# Sheet5.net
KiCad netlist of a schematic drawn in Altium Designer
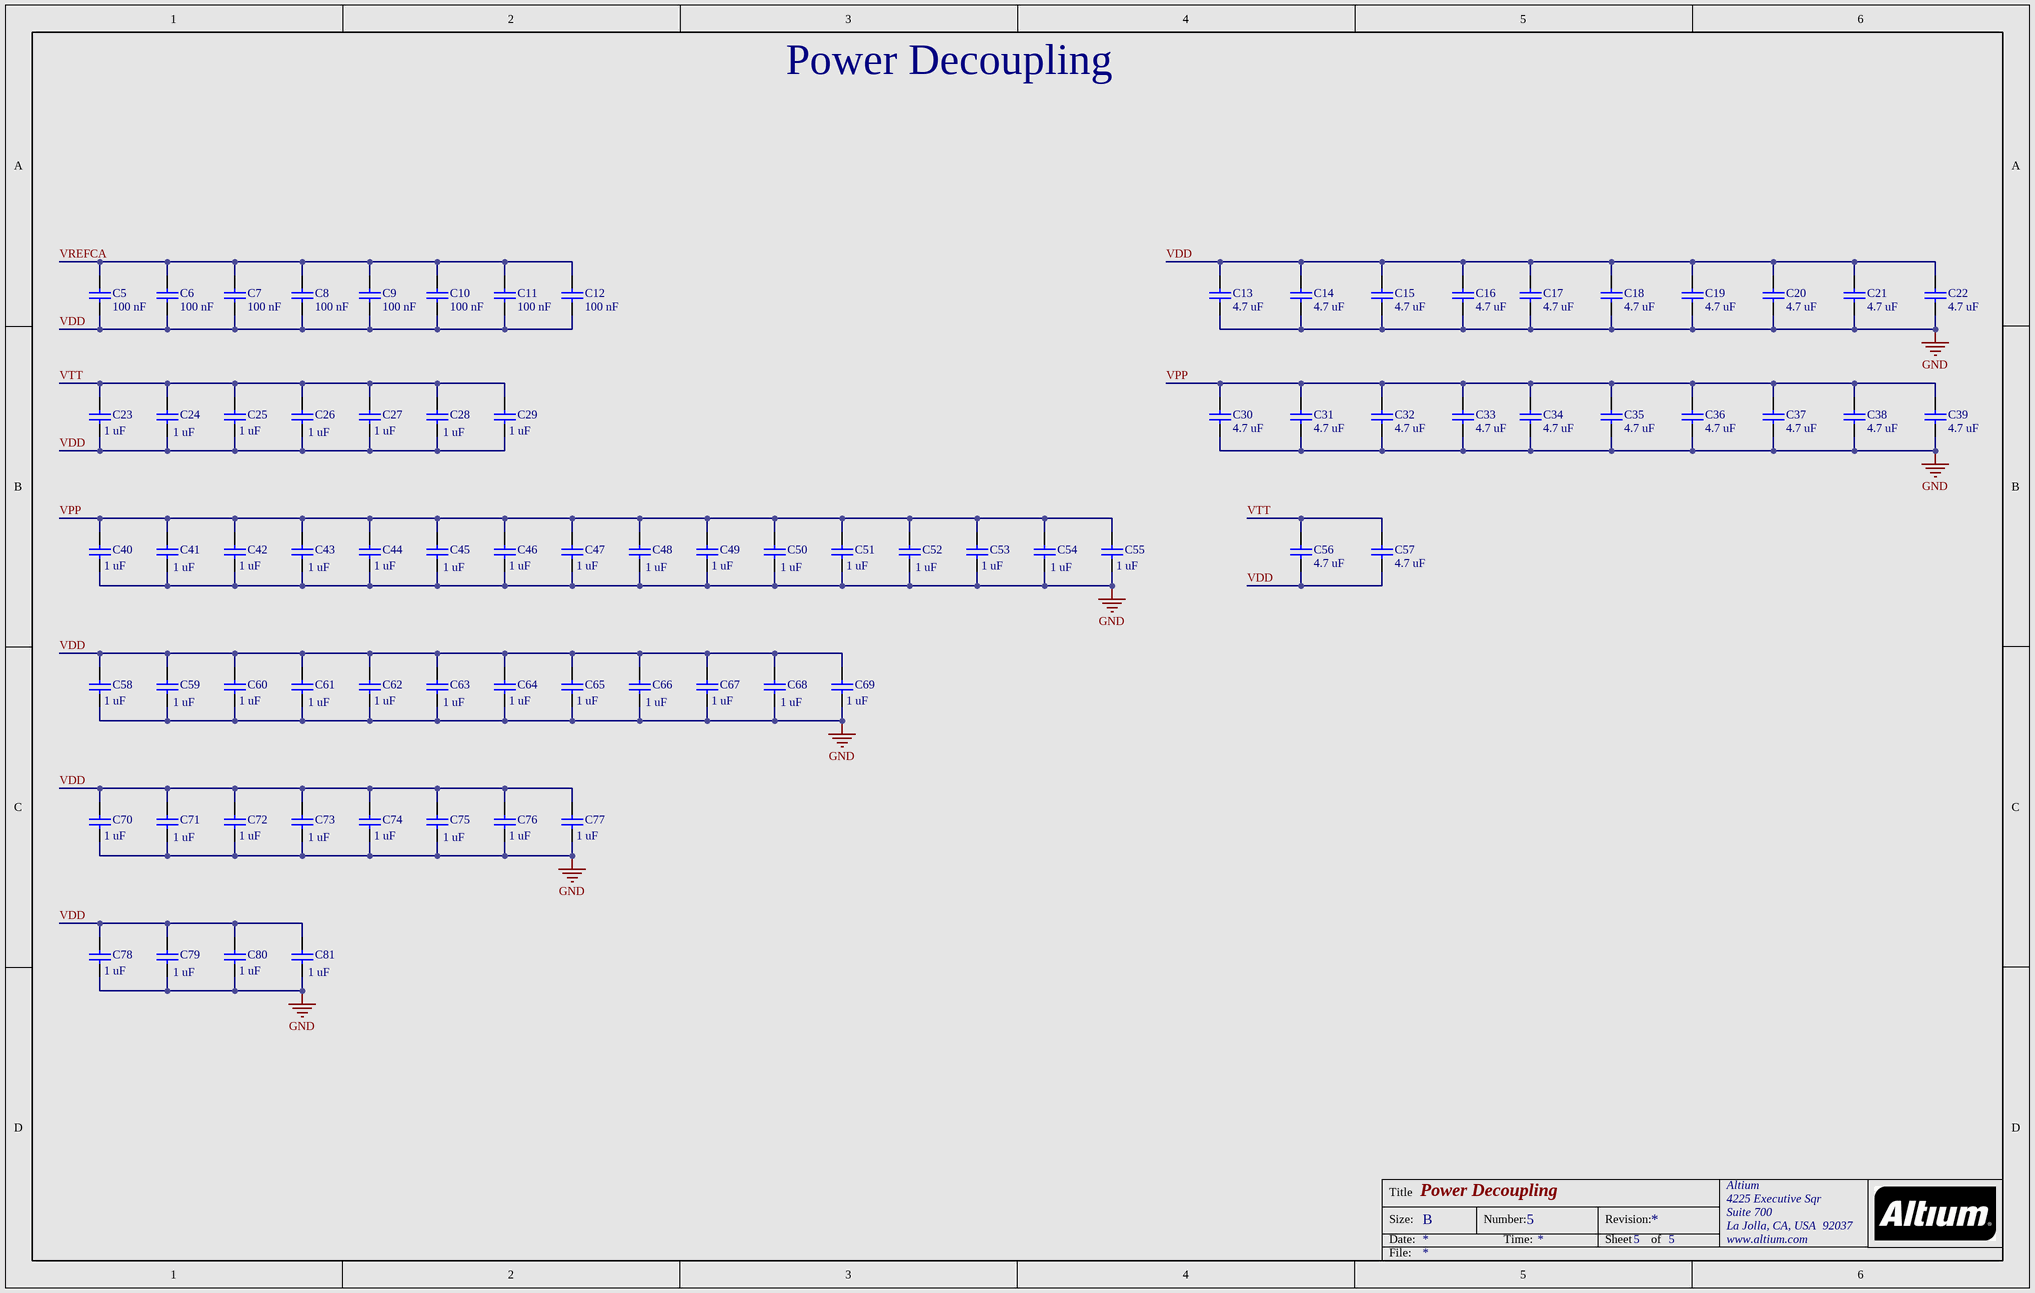
[diagram p0: Sheet5.SchDoc]

(export (version "E")
  (design (tool "Eeschema 10.0.6"))
  (components
    (comp (ref "C5")
      (value "C1005X7R1E104M")
      (footprint "CAPC1005X55X10LL05")
      (description "Chip Capacitor, 0.1 uF, +/- 20%, 25 V, -55 to 125 degC, 0402 (1005 Metric), RoHS, Tape and Reel")
      (fields (field (name "TOLERANCE") "20%") (field (name "CAPACITANCE") "100 nF"))
      (libsource (lib "Altium Content Vault") (part "CMP-1663-00009-2"))
    )
    (comp (ref "C6")
      (value "C1005X7R1E104M")
      (footprint "CAPC1005X55X10LL05")
      (description "Chip Capacitor, 0.1 uF, +/- 20%, 25 V, -55 to 125 degC, 0402 (1005 Metric), RoHS, Tape and Reel")
      (fields (field (name "TOLERANCE") "20%") (field (name "CAPACITANCE") "100 nF"))
      (libsource (lib "Altium Content Vault") (part "CMP-1663-00009-2"))
    )
    (comp (ref "C7")
      (value "C1005X7R1E104M")
      (footprint "CAPC1005X55X10LL05")
      (description "Chip Capacitor, 0.1 uF, +/- 20%, 25 V, -55 to 125 degC, 0402 (1005 Metric), RoHS, Tape and Reel")
      (fields (field (name "TOLERANCE") "20%") (field (name "CAPACITANCE") "100 nF"))
      (libsource (lib "Altium Content Vault") (part "CMP-1663-00009-2"))
    )
    (comp (ref "C8")
      (value "C1005X7R1E104M")
      (footprint "CAPC1005X55X10LL05")
      (description "Chip Capacitor, 0.1 uF, +/- 20%, 25 V, -55 to 125 degC, 0402 (1005 Metric), RoHS, Tape and Reel")
      (fields (field (name "TOLERANCE") "20%") (field (name "CAPACITANCE") "100 nF"))
      (libsource (lib "Altium Content Vault") (part "CMP-1663-00009-2"))
    )
    (comp (ref "C9")
      (value "C1005X7R1E104M")
      (footprint "CAPC1005X55X10LL05")
      (description "Chip Capacitor, 0.1 uF, +/- 20%, 25 V, -55 to 125 degC, 0402 (1005 Metric), RoHS, Tape and Reel")
      (fields (field (name "TOLERANCE") "20%") (field (name "CAPACITANCE") "100 nF"))
      (libsource (lib "Altium Content Vault") (part "CMP-1663-00009-2"))
    )
    (comp (ref "C10")
      (value "C1005X7R1E104M")
      (footprint "CAPC1005X55X10LL05")
      (description "Chip Capacitor, 0.1 uF, +/- 20%, 25 V, -55 to 125 degC, 0402 (1005 Metric), RoHS, Tape and Reel")
      (fields (field (name "TOLERANCE") "20%") (field (name "CAPACITANCE") "100 nF"))
      (libsource (lib "Altium Content Vault") (part "CMP-1663-00009-2"))
    )
    (comp (ref "C11")
      (value "C1005X7R1E104M")
      (footprint "CAPC1005X55X10LL05")
      (description "Chip Capacitor, 0.1 uF, +/- 20%, 25 V, -55 to 125 degC, 0402 (1005 Metric), RoHS, Tape and Reel")
      (fields (field (name "TOLERANCE") "20%") (field (name "CAPACITANCE") "100 nF"))
      (libsource (lib "Altium Content Vault") (part "CMP-1663-00009-2"))
    )
    (comp (ref "C12")
      (value "C1005X7R1E104M")
      (footprint "CAPC1005X55X10LL05")
      (description "Chip Capacitor, 0.1 uF, +/- 20%, 25 V, -55 to 125 degC, 0402 (1005 Metric), RoHS, Tape and Reel")
      (fields (field (name "TOLERANCE") "20%") (field (name "CAPACITANCE") "100 nF"))
      (libsource (lib "Altium Content Vault") (part "CMP-1663-00009-2"))
    )
    (comp (ref "C13")
      (value "GRM188R60J475KE19D")
      (footprint "CAPC1608X90X35ML10T15")
      (description "Chip Capacitor, 4.7 uF, +/- 10%, 6.3 V, -55 to 85 degC, 0603 (1608 Metric), RoHS, Tape and Reel")
      (fields (field (name "TOLERANCE") "10%") (field (name "CAPACITANCE") "4.7 uF"))
      (libsource (lib "Altium Content Vault") (part "CMP-2006-02799-2"))
    )
    (comp (ref "C14")
      (value "GRM188R60J475KE19D")
      (footprint "CAPC1608X90X35ML10T15")
      (description "Chip Capacitor, 4.7 uF, +/- 10%, 6.3 V, -55 to 85 degC, 0603 (1608 Metric), RoHS, Tape and Reel")
      (fields (field (name "TOLERANCE") "10%") (field (name "CAPACITANCE") "4.7 uF"))
      (libsource (lib "Altium Content Vault") (part "CMP-2006-02799-2"))
    )
    (comp (ref "C15")
      (value "GRM188R60J475KE19D")
      (footprint "CAPC1608X90X35ML10T15")
      (description "Chip Capacitor, 4.7 uF, +/- 10%, 6.3 V, -55 to 85 degC, 0603 (1608 Metric), RoHS, Tape and Reel")
      (fields (field (name "TOLERANCE") "10%") (field (name "CAPACITANCE") "4.7 uF"))
      (libsource (lib "Altium Content Vault") (part "CMP-2006-02799-2"))
    )
    (comp (ref "C16")
      (value "GRM188R60J475KE19D")
      (footprint "CAPC1608X90X35ML10T15")
      (description "Chip Capacitor, 4.7 uF, +/- 10%, 6.3 V, -55 to 85 degC, 0603 (1608 Metric), RoHS, Tape and Reel")
      (fields (field (name "TOLERANCE") "10%") (field (name "CAPACITANCE") "4.7 uF"))
      (libsource (lib "Altium Content Vault") (part "CMP-2006-02799-2"))
    )
    (comp (ref "C17")
      (value "GRM188R60J475KE19D")
      (footprint "CAPC1608X90X35ML10T15")
      (description "Chip Capacitor, 4.7 uF, +/- 10%, 6.3 V, -55 to 85 degC, 0603 (1608 Metric), RoHS, Tape and Reel")
      (fields (field (name "TOLERANCE") "10%") (field (name "CAPACITANCE") "4.7 uF"))
      (libsource (lib "Altium Content Vault") (part "CMP-2006-02799-2"))
    )
    (comp (ref "C18")
      (value "GRM188R60J475KE19D")
      (footprint "CAPC1608X90X35ML10T15")
      (description "Chip Capacitor, 4.7 uF, +/- 10%, 6.3 V, -55 to 85 degC, 0603 (1608 Metric), RoHS, Tape and Reel")
      (fields (field (name "TOLERANCE") "10%") (field (name "CAPACITANCE") "4.7 uF"))
      (libsource (lib "Altium Content Vault") (part "CMP-2006-02799-2"))
    )
    (comp (ref "C19")
      (value "GRM188R60J475KE19D")
      (footprint "CAPC1608X90X35ML10T15")
      (description "Chip Capacitor, 4.7 uF, +/- 10%, 6.3 V, -55 to 85 degC, 0603 (1608 Metric), RoHS, Tape and Reel")
      (fields (field (name "TOLERANCE") "10%") (field (name "CAPACITANCE") "4.7 uF"))
      (libsource (lib "Altium Content Vault") (part "CMP-2006-02799-2"))
    )
    (comp (ref "C20")
      (value "GRM188R60J475KE19D")
      (footprint "CAPC1608X90X35ML10T15")
      (description "Chip Capacitor, 4.7 uF, +/- 10%, 6.3 V, -55 to 85 degC, 0603 (1608 Metric), RoHS, Tape and Reel")
      (fields (field (name "TOLERANCE") "10%") (field (name "CAPACITANCE") "4.7 uF"))
      (libsource (lib "Altium Content Vault") (part "CMP-2006-02799-2"))
    )
    (comp (ref "C21")
      (value "GRM188R60J475KE19D")
      (footprint "CAPC1608X90X35ML10T15")
      (description "Chip Capacitor, 4.7 uF, +/- 10%, 6.3 V, -55 to 85 degC, 0603 (1608 Metric), RoHS, Tape and Reel")
      (fields (field (name "TOLERANCE") "10%") (field (name "CAPACITANCE") "4.7 uF"))
      (libsource (lib "Altium Content Vault") (part "CMP-2006-02799-2"))
    )
    (comp (ref "C22")
      (value "GRM188R60J475KE19D")
      (footprint "CAPC1608X90X35ML10T15")
      (description "Chip Capacitor, 4.7 uF, +/- 10%, 6.3 V, -55 to 85 degC, 0603 (1608 Metric), RoHS, Tape and Reel")
      (fields (field (name "TOLERANCE") "10%") (field (name "CAPACITANCE") "4.7 uF"))
      (libsource (lib "Altium Content Vault") (part "CMP-2006-02799-2"))
    )
    (comp (ref "C23")
      (value "CGB2A1X5R1E105K033BC")
      (footprint "CAPC1005X33X10LL5")
      (description "Chip Capacitor, 1 uF, +/- 10%, 25 V, -55 to 85 degC, 0402 (1005 Metric), RoHS, Tape and Reel")
      (fields (field (name "CAPACITANCE") "1 uF") (field (name "TOLERANCE") "10%"))
      (libsource (lib "Altium Content Vault") (part "CMP-1663-00006-2"))
    )
    (comp (ref "C24")
      (value "CGB2A1X5R1E105K033BC")
      (footprint "CAPC1005X33X10LL5")
      (description "Chip Capacitor, 1 uF, +/- 10%, 25 V, -55 to 85 degC, 0402 (1005 Metric), RoHS, Tape and Reel")
      (fields (field (name "CAPACITANCE") "1 uF") (field (name "TOLERANCE") "10%"))
      (libsource (lib "Altium Content Vault") (part "CMP-1663-00006-2"))
    )
    (comp (ref "C25")
      (value "CGB2A1X5R1E105K033BC")
      (footprint "CAPC1005X33X10LL5")
      (description "Chip Capacitor, 1 uF, +/- 10%, 25 V, -55 to 85 degC, 0402 (1005 Metric), RoHS, Tape and Reel")
      (fields (field (name "CAPACITANCE") "1 uF") (field (name "TOLERANCE") "10%"))
      (libsource (lib "Altium Content Vault") (part "CMP-1663-00006-2"))
    )
    (comp (ref "C26")
      (value "CGB2A1X5R1E105K033BC")
      (footprint "CAPC1005X33X10LL5")
      (description "Chip Capacitor, 1 uF, +/- 10%, 25 V, -55 to 85 degC, 0402 (1005 Metric), RoHS, Tape and Reel")
      (fields (field (name "CAPACITANCE") "1 uF") (field (name "TOLERANCE") "10%"))
      (libsource (lib "Altium Content Vault") (part "CMP-1663-00006-2"))
    )
    (comp (ref "C27")
      (value "CGB2A1X5R1E105K033BC")
      (footprint "CAPC1005X33X10LL5")
      (description "Chip Capacitor, 1 uF, +/- 10%, 25 V, -55 to 85 degC, 0402 (1005 Metric), RoHS, Tape and Reel")
      (fields (field (name "CAPACITANCE") "1 uF") (field (name "TOLERANCE") "10%"))
      (libsource (lib "Altium Content Vault") (part "CMP-1663-00006-2"))
    )
    (comp (ref "C28")
      (value "CGB2A1X5R1E105K033BC")
      (footprint "CAPC1005X33X10LL5")
      (description "Chip Capacitor, 1 uF, +/- 10%, 25 V, -55 to 85 degC, 0402 (1005 Metric), RoHS, Tape and Reel")
      (fields (field (name "CAPACITANCE") "1 uF") (field (name "TOLERANCE") "10%"))
      (libsource (lib "Altium Content Vault") (part "CMP-1663-00006-2"))
    )
    (comp (ref "C29")
      (value "CGB2A1X5R1E105K033BC")
      (footprint "CAPC1005X33X10LL5")
      (description "Chip Capacitor, 1 uF, +/- 10%, 25 V, -55 to 85 degC, 0402 (1005 Metric), RoHS, Tape and Reel")
      (fields (field (name "CAPACITANCE") "1 uF") (field (name "TOLERANCE") "10%"))
      (libsource (lib "Altium Content Vault") (part "CMP-1663-00006-2"))
    )
    (comp (ref "C30")
      (value "GRM188R60J475KE19D")
      (footprint "CAPC1608X90X35ML10T15")
      (description "Chip Capacitor, 4.7 uF, +/- 10%, 6.3 V, -55 to 85 degC, 0603 (1608 Metric), RoHS, Tape and Reel")
      (fields (field (name "TOLERANCE") "10%") (field (name "CAPACITANCE") "4.7 uF"))
      (libsource (lib "Altium Content Vault") (part "CMP-2006-02799-2"))
    )
    (comp (ref "C31")
      (value "GRM188R60J475KE19D")
      (footprint "CAPC1608X90X35ML10T15")
      (description "Chip Capacitor, 4.7 uF, +/- 10%, 6.3 V, -55 to 85 degC, 0603 (1608 Metric), RoHS, Tape and Reel")
      (fields (field (name "TOLERANCE") "10%") (field (name "CAPACITANCE") "4.7 uF"))
      (libsource (lib "Altium Content Vault") (part "CMP-2006-02799-2"))
    )
    (comp (ref "C32")
      (value "GRM188R60J475KE19D")
      (footprint "CAPC1608X90X35ML10T15")
      (description "Chip Capacitor, 4.7 uF, +/- 10%, 6.3 V, -55 to 85 degC, 0603 (1608 Metric), RoHS, Tape and Reel")
      (fields (field (name "TOLERANCE") "10%") (field (name "CAPACITANCE") "4.7 uF"))
      (libsource (lib "Altium Content Vault") (part "CMP-2006-02799-2"))
    )
    (comp (ref "C33")
      (value "GRM188R60J475KE19D")
      (footprint "CAPC1608X90X35ML10T15")
      (description "Chip Capacitor, 4.7 uF, +/- 10%, 6.3 V, -55 to 85 degC, 0603 (1608 Metric), RoHS, Tape and Reel")
      (fields (field (name "TOLERANCE") "10%") (field (name "CAPACITANCE") "4.7 uF"))
      (libsource (lib "Altium Content Vault") (part "CMP-2006-02799-2"))
    )
    (comp (ref "C34")
      (value "GRM188R60J475KE19D")
      (footprint "CAPC1608X90X35ML10T15")
      (description "Chip Capacitor, 4.7 uF, +/- 10%, 6.3 V, -55 to 85 degC, 0603 (1608 Metric), RoHS, Tape and Reel")
      (fields (field (name "TOLERANCE") "10%") (field (name "CAPACITANCE") "4.7 uF"))
      (libsource (lib "Altium Content Vault") (part "CMP-2006-02799-2"))
    )
    (comp (ref "C35")
      (value "GRM188R60J475KE19D")
      (footprint "CAPC1608X90X35ML10T15")
      (description "Chip Capacitor, 4.7 uF, +/- 10%, 6.3 V, -55 to 85 degC, 0603 (1608 Metric), RoHS, Tape and Reel")
      (fields (field (name "TOLERANCE") "10%") (field (name "CAPACITANCE") "4.7 uF"))
      (libsource (lib "Altium Content Vault") (part "CMP-2006-02799-2"))
    )
    (comp (ref "C36")
      (value "GRM188R60J475KE19D")
      (footprint "CAPC1608X90X35ML10T15")
      (description "Chip Capacitor, 4.7 uF, +/- 10%, 6.3 V, -55 to 85 degC, 0603 (1608 Metric), RoHS, Tape and Reel")
      (fields (field (name "TOLERANCE") "10%") (field (name "CAPACITANCE") "4.7 uF"))
      (libsource (lib "Altium Content Vault") (part "CMP-2006-02799-2"))
    )
    (comp (ref "C37")
      (value "GRM188R60J475KE19D")
      (footprint "CAPC1608X90X35ML10T15")
      (description "Chip Capacitor, 4.7 uF, +/- 10%, 6.3 V, -55 to 85 degC, 0603 (1608 Metric), RoHS, Tape and Reel")
      (fields (field (name "TOLERANCE") "10%") (field (name "CAPACITANCE") "4.7 uF"))
      (libsource (lib "Altium Content Vault") (part "CMP-2006-02799-2"))
    )
    (comp (ref "C38")
      (value "GRM188R60J475KE19D")
      (footprint "CAPC1608X90X35ML10T15")
      (description "Chip Capacitor, 4.7 uF, +/- 10%, 6.3 V, -55 to 85 degC, 0603 (1608 Metric), RoHS, Tape and Reel")
      (fields (field (name "TOLERANCE") "10%") (field (name "CAPACITANCE") "4.7 uF"))
      (libsource (lib "Altium Content Vault") (part "CMP-2006-02799-2"))
    )
    (comp (ref "C39")
      (value "GRM188R60J475KE19D")
      (footprint "CAPC1608X90X35ML10T15")
      (description "Chip Capacitor, 4.7 uF, +/- 10%, 6.3 V, -55 to 85 degC, 0603 (1608 Metric), RoHS, Tape and Reel")
      (fields (field (name "TOLERANCE") "10%") (field (name "CAPACITANCE") "4.7 uF"))
      (libsource (lib "Altium Content Vault") (part "CMP-2006-02799-2"))
    )
    (comp (ref "C40")
      (value "CGB2A1X5R1E105K033BC")
      (footprint "CAPC1005X33X10LL5")
      (description "Chip Capacitor, 1 uF, +/- 10%, 25 V, -55 to 85 degC, 0402 (1005 Metric), RoHS, Tape and Reel")
      (fields (field (name "CAPACITANCE") "1 uF") (field (name "TOLERANCE") "10%"))
      (libsource (lib "Altium Content Vault") (part "CMP-1663-00006-2"))
    )
    (comp (ref "C41")
      (value "CGB2A1X5R1E105K033BC")
      (footprint "CAPC1005X33X10LL5")
      (description "Chip Capacitor, 1 uF, +/- 10%, 25 V, -55 to 85 degC, 0402 (1005 Metric), RoHS, Tape and Reel")
      (fields (field (name "CAPACITANCE") "1 uF") (field (name "TOLERANCE") "10%"))
      (libsource (lib "Altium Content Vault") (part "CMP-1663-00006-2"))
    )
    (comp (ref "C42")
      (value "CGB2A1X5R1E105K033BC")
      (footprint "CAPC1005X33X10LL5")
      (description "Chip Capacitor, 1 uF, +/- 10%, 25 V, -55 to 85 degC, 0402 (1005 Metric), RoHS, Tape and Reel")
      (fields (field (name "CAPACITANCE") "1 uF") (field (name "TOLERANCE") "10%"))
      (libsource (lib "Altium Content Vault") (part "CMP-1663-00006-2"))
    )
    (comp (ref "C43")
      (value "CGB2A1X5R1E105K033BC")
      (footprint "CAPC1005X33X10LL5")
      (description "Chip Capacitor, 1 uF, +/- 10%, 25 V, -55 to 85 degC, 0402 (1005 Metric), RoHS, Tape and Reel")
      (fields (field (name "CAPACITANCE") "1 uF") (field (name "TOLERANCE") "10%"))
      (libsource (lib "Altium Content Vault") (part "CMP-1663-00006-2"))
    )
    (comp (ref "C44")
      (value "CGB2A1X5R1E105K033BC")
      (footprint "CAPC1005X33X10LL5")
      (description "Chip Capacitor, 1 uF, +/- 10%, 25 V, -55 to 85 degC, 0402 (1005 Metric), RoHS, Tape and Reel")
      (fields (field (name "CAPACITANCE") "1 uF") (field (name "TOLERANCE") "10%"))
      (libsource (lib "Altium Content Vault") (part "CMP-1663-00006-2"))
    )
    (comp (ref "C45")
      (value "CGB2A1X5R1E105K033BC")
      (footprint "CAPC1005X33X10LL5")
      (description "Chip Capacitor, 1 uF, +/- 10%, 25 V, -55 to 85 degC, 0402 (1005 Metric), RoHS, Tape and Reel")
      (fields (field (name "CAPACITANCE") "1 uF") (field (name "TOLERANCE") "10%"))
      (libsource (lib "Altium Content Vault") (part "CMP-1663-00006-2"))
    )
    (comp (ref "C46")
      (value "CGB2A1X5R1E105K033BC")
      (footprint "CAPC1005X33X10LL5")
      (description "Chip Capacitor, 1 uF, +/- 10%, 25 V, -55 to 85 degC, 0402 (1005 Metric), RoHS, Tape and Reel")
      (fields (field (name "CAPACITANCE") "1 uF") (field (name "TOLERANCE") "10%"))
      (libsource (lib "Altium Content Vault") (part "CMP-1663-00006-2"))
    )
    (comp (ref "C47")
      (value "CGB2A1X5R1E105K033BC")
      (footprint "CAPC1005X33X10LL5")
      (description "Chip Capacitor, 1 uF, +/- 10%, 25 V, -55 to 85 degC, 0402 (1005 Metric), RoHS, Tape and Reel")
      (fields (field (name "CAPACITANCE") "1 uF") (field (name "TOLERANCE") "10%"))
      (libsource (lib "Altium Content Vault") (part "CMP-1663-00006-2"))
    )
    (comp (ref "C48")
      (value "CGB2A1X5R1E105K033BC")
      (footprint "CAPC1005X33X10LL5")
      (description "Chip Capacitor, 1 uF, +/- 10%, 25 V, -55 to 85 degC, 0402 (1005 Metric), RoHS, Tape and Reel")
      (fields (field (name "CAPACITANCE") "1 uF") (field (name "TOLERANCE") "10%"))
      (libsource (lib "Altium Content Vault") (part "CMP-1663-00006-2"))
    )
    (comp (ref "C49")
      (value "CGB2A1X5R1E105K033BC")
      (footprint "CAPC1005X33X10LL5")
      (description "Chip Capacitor, 1 uF, +/- 10%, 25 V, -55 to 85 degC, 0402 (1005 Metric), RoHS, Tape and Reel")
      (fields (field (name "CAPACITANCE") "1 uF") (field (name "TOLERANCE") "10%"))
      (libsource (lib "Altium Content Vault") (part "CMP-1663-00006-2"))
    )
    (comp (ref "C50")
      (value "CGB2A1X5R1E105K033BC")
      (footprint "CAPC1005X33X10LL5")
      (description "Chip Capacitor, 1 uF, +/- 10%, 25 V, -55 to 85 degC, 0402 (1005 Metric), RoHS, Tape and Reel")
      (fields (field (name "CAPACITANCE") "1 uF") (field (name "TOLERANCE") "10%"))
      (libsource (lib "Altium Content Vault") (part "CMP-1663-00006-2"))
    )
    (comp (ref "C51")
      (value "CGB2A1X5R1E105K033BC")
      (footprint "CAPC1005X33X10LL5")
      (description "Chip Capacitor, 1 uF, +/- 10%, 25 V, -55 to 85 degC, 0402 (1005 Metric), RoHS, Tape and Reel")
      (fields (field (name "CAPACITANCE") "1 uF") (field (name "TOLERANCE") "10%"))
      (libsource (lib "Altium Content Vault") (part "CMP-1663-00006-2"))
    )
    (comp (ref "C52")
      (value "CGB2A1X5R1E105K033BC")
      (footprint "CAPC1005X33X10LL5")
      (description "Chip Capacitor, 1 uF, +/- 10%, 25 V, -55 to 85 degC, 0402 (1005 Metric), RoHS, Tape and Reel")
      (fields (field (name "CAPACITANCE") "1 uF") (field (name "TOLERANCE") "10%"))
      (libsource (lib "Altium Content Vault") (part "CMP-1663-00006-2"))
    )
    (comp (ref "C53")
      (value "CGB2A1X5R1E105K033BC")
      (footprint "CAPC1005X33X10LL5")
      (description "Chip Capacitor, 1 uF, +/- 10%, 25 V, -55 to 85 degC, 0402 (1005 Metric), RoHS, Tape and Reel")
      (fields (field (name "CAPACITANCE") "1 uF") (field (name "TOLERANCE") "10%"))
      (libsource (lib "Altium Content Vault") (part "CMP-1663-00006-2"))
    )
    (comp (ref "C54")
      (value "CGB2A1X5R1E105K033BC")
      (footprint "CAPC1005X33X10LL5")
      (description "Chip Capacitor, 1 uF, +/- 10%, 25 V, -55 to 85 degC, 0402 (1005 Metric), RoHS, Tape and Reel")
      (fields (field (name "CAPACITANCE") "1 uF") (field (name "TOLERANCE") "10%"))
      (libsource (lib "Altium Content Vault") (part "CMP-1663-00006-2"))
    )
    (comp (ref "C55")
      (value "CGB2A1X5R1E105K033BC")
      (footprint "CAPC1005X33X10LL5")
      (description "Chip Capacitor, 1 uF, +/- 10%, 25 V, -55 to 85 degC, 0402 (1005 Metric), RoHS, Tape and Reel")
      (fields (field (name "CAPACITANCE") "1 uF") (field (name "TOLERANCE") "10%"))
      (libsource (lib "Altium Content Vault") (part "CMP-1663-00006-2"))
    )
    (comp (ref "C56")
      (value "GRM188R60J475KE19D")
      (footprint "CAPC1608X90X35ML10T15")
      (description "Chip Capacitor, 4.7 uF, +/- 10%, 6.3 V, -55 to 85 degC, 0603 (1608 Metric), RoHS, Tape and Reel")
      (fields (field (name "TOLERANCE") "10%") (field (name "CAPACITANCE") "4.7 uF"))
      (libsource (lib "Altium Content Vault") (part "CMP-2006-02799-2"))
    )
    (comp (ref "C57")
      (value "GRM188R60J475KE19D")
      (footprint "CAPC1608X90X35ML10T15")
      (description "Chip Capacitor, 4.7 uF, +/- 10%, 6.3 V, -55 to 85 degC, 0603 (1608 Metric), RoHS, Tape and Reel")
      (fields (field (name "TOLERANCE") "10%") (field (name "CAPACITANCE") "4.7 uF"))
      (libsource (lib "Altium Content Vault") (part "CMP-2006-02799-2"))
    )
    (comp (ref "C58")
      (value "CGB2A1X5R1E105K033BC")
      (footprint "CAPC1005X33X10LL5")
      (description "Chip Capacitor, 1 uF, +/- 10%, 25 V, -55 to 85 degC, 0402 (1005 Metric), RoHS, Tape and Reel")
      (fields (field (name "CAPACITANCE") "1 uF") (field (name "TOLERANCE") "10%"))
      (libsource (lib "Altium Content Vault") (part "CMP-1663-00006-2"))
    )
    (comp (ref "C59")
      (value "CGB2A1X5R1E105K033BC")
      (footprint "CAPC1005X33X10LL5")
      (description "Chip Capacitor, 1 uF, +/- 10%, 25 V, -55 to 85 degC, 0402 (1005 Metric), RoHS, Tape and Reel")
      (fields (field (name "CAPACITANCE") "1 uF") (field (name "TOLERANCE") "10%"))
      (libsource (lib "Altium Content Vault") (part "CMP-1663-00006-2"))
    )
    (comp (ref "C60")
      (value "CGB2A1X5R1E105K033BC")
      (footprint "CAPC1005X33X10LL5")
      (description "Chip Capacitor, 1 uF, +/- 10%, 25 V, -55 to 85 degC, 0402 (1005 Metric), RoHS, Tape and Reel")
      (fields (field (name "CAPACITANCE") "1 uF") (field (name "TOLERANCE") "10%"))
      (libsource (lib "Altium Content Vault") (part "CMP-1663-00006-2"))
    )
    (comp (ref "C61")
      (value "CGB2A1X5R1E105K033BC")
      (footprint "CAPC1005X33X10LL5")
      (description "Chip Capacitor, 1 uF, +/- 10%, 25 V, -55 to 85 degC, 0402 (1005 Metric), RoHS, Tape and Reel")
      (fields (field (name "CAPACITANCE") "1 uF") (field (name "TOLERANCE") "10%"))
      (libsource (lib "Altium Content Vault") (part "CMP-1663-00006-2"))
    )
    (comp (ref "C62")
      (value "CGB2A1X5R1E105K033BC")
      (footprint "CAPC1005X33X10LL5")
      (description "Chip Capacitor, 1 uF, +/- 10%, 25 V, -55 to 85 degC, 0402 (1005 Metric), RoHS, Tape and Reel")
      (fields (field (name "CAPACITANCE") "1 uF") (field (name "TOLERANCE") "10%"))
      (libsource (lib "Altium Content Vault") (part "CMP-1663-00006-2"))
    )
    (comp (ref "C63")
      (value "CGB2A1X5R1E105K033BC")
      (footprint "CAPC1005X33X10LL5")
      (description "Chip Capacitor, 1 uF, +/- 10%, 25 V, -55 to 85 degC, 0402 (1005 Metric), RoHS, Tape and Reel")
      (fields (field (name "CAPACITANCE") "1 uF") (field (name "TOLERANCE") "10%"))
      (libsource (lib "Altium Content Vault") (part "CMP-1663-00006-2"))
    )
    (comp (ref "C64")
      (value "CGB2A1X5R1E105K033BC")
      (footprint "CAPC1005X33X10LL5")
      (description "Chip Capacitor, 1 uF, +/- 10%, 25 V, -55 to 85 degC, 0402 (1005 Metric), RoHS, Tape and Reel")
      (fields (field (name "CAPACITANCE") "1 uF") (field (name "TOLERANCE") "10%"))
      (libsource (lib "Altium Content Vault") (part "CMP-1663-00006-2"))
    )
    (comp (ref "C65")
      (value "CGB2A1X5R1E105K033BC")
      (footprint "CAPC1005X33X10LL5")
      (description "Chip Capacitor, 1 uF, +/- 10%, 25 V, -55 to 85 degC, 0402 (1005 Metric), RoHS, Tape and Reel")
      (fields (field (name "CAPACITANCE") "1 uF") (field (name "TOLERANCE") "10%"))
      (libsource (lib "Altium Content Vault") (part "CMP-1663-00006-2"))
    )
    (comp (ref "C66")
      (value "CGB2A1X5R1E105K033BC")
      (footprint "CAPC1005X33X10LL5")
      (description "Chip Capacitor, 1 uF, +/- 10%, 25 V, -55 to 85 degC, 0402 (1005 Metric), RoHS, Tape and Reel")
      (fields (field (name "CAPACITANCE") "1 uF") (field (name "TOLERANCE") "10%"))
      (libsource (lib "Altium Content Vault") (part "CMP-1663-00006-2"))
    )
    (comp (ref "C67")
      (value "CGB2A1X5R1E105K033BC")
      (footprint "CAPC1005X33X10LL5")
      (description "Chip Capacitor, 1 uF, +/- 10%, 25 V, -55 to 85 degC, 0402 (1005 Metric), RoHS, Tape and Reel")
      (fields (field (name "CAPACITANCE") "1 uF") (field (name "TOLERANCE") "10%"))
      (libsource (lib "Altium Content Vault") (part "CMP-1663-00006-2"))
    )
    (comp (ref "C68")
      (value "CGB2A1X5R1E105K033BC")
      (footprint "CAPC1005X33X10LL5")
      (description "Chip Capacitor, 1 uF, +/- 10%, 25 V, -55 to 85 degC, 0402 (1005 Metric), RoHS, Tape and Reel")
      (fields (field (name "CAPACITANCE") "1 uF") (field (name "TOLERANCE") "10%"))
      (libsource (lib "Altium Content Vault") (part "CMP-1663-00006-2"))
    )
    (comp (ref "C69")
      (value "CGB2A1X5R1E105K033BC")
      (footprint "CAPC1005X33X10LL5")
      (description "Chip Capacitor, 1 uF, +/- 10%, 25 V, -55 to 85 degC, 0402 (1005 Metric), RoHS, Tape and Reel")
      (fields (field (name "CAPACITANCE") "1 uF") (field (name "TOLERANCE") "10%"))
      (libsource (lib "Altium Content Vault") (part "CMP-1663-00006-2"))
    )
    (comp (ref "C70")
      (value "CGB2A1X5R1E105K033BC")
      (footprint "CAPC1005X33X10LL5")
      (description "Chip Capacitor, 1 uF, +/- 10%, 25 V, -55 to 85 degC, 0402 (1005 Metric), RoHS, Tape and Reel")
      (fields (field (name "CAPACITANCE") "1 uF") (field (name "TOLERANCE") "10%"))
      (libsource (lib "Altium Content Vault") (part "CMP-1663-00006-2"))
    )
    (comp (ref "C71")
      (value "CGB2A1X5R1E105K033BC")
      (footprint "CAPC1005X33X10LL5")
      (description "Chip Capacitor, 1 uF, +/- 10%, 25 V, -55 to 85 degC, 0402 (1005 Metric), RoHS, Tape and Reel")
      (fields (field (name "CAPACITANCE") "1 uF") (field (name "TOLERANCE") "10%"))
      (libsource (lib "Altium Content Vault") (part "CMP-1663-00006-2"))
    )
    (comp (ref "C72")
      (value "CGB2A1X5R1E105K033BC")
      (footprint "CAPC1005X33X10LL5")
      (description "Chip Capacitor, 1 uF, +/- 10%, 25 V, -55 to 85 degC, 0402 (1005 Metric), RoHS, Tape and Reel")
      (fields (field (name "CAPACITANCE") "1 uF") (field (name "TOLERANCE") "10%"))
      (libsource (lib "Altium Content Vault") (part "CMP-1663-00006-2"))
    )
    (comp (ref "C73")
      (value "CGB2A1X5R1E105K033BC")
      (footprint "CAPC1005X33X10LL5")
      (description "Chip Capacitor, 1 uF, +/- 10%, 25 V, -55 to 85 degC, 0402 (1005 Metric), RoHS, Tape and Reel")
      (fields (field (name "CAPACITANCE") "1 uF") (field (name "TOLERANCE") "10%"))
      (libsource (lib "Altium Content Vault") (part "CMP-1663-00006-2"))
    )
    (comp (ref "C74")
      (value "CGB2A1X5R1E105K033BC")
      (footprint "CAPC1005X33X10LL5")
      (description "Chip Capacitor, 1 uF, +/- 10%, 25 V, -55 to 85 degC, 0402 (1005 Metric), RoHS, Tape and Reel")
      (fields (field (name "CAPACITANCE") "1 uF") (field (name "TOLERANCE") "10%"))
      (libsource (lib "Altium Content Vault") (part "CMP-1663-00006-2"))
    )
    (comp (ref "C75")
      (value "CGB2A1X5R1E105K033BC")
      (footprint "CAPC1005X33X10LL5")
      (description "Chip Capacitor, 1 uF, +/- 10%, 25 V, -55 to 85 degC, 0402 (1005 Metric), RoHS, Tape and Reel")
      (fields (field (name "CAPACITANCE") "1 uF") (field (name "TOLERANCE") "10%"))
      (libsource (lib "Altium Content Vault") (part "CMP-1663-00006-2"))
    )
    (comp (ref "C76")
      (value "CGB2A1X5R1E105K033BC")
      (footprint "CAPC1005X33X10LL5")
      (description "Chip Capacitor, 1 uF, +/- 10%, 25 V, -55 to 85 degC, 0402 (1005 Metric), RoHS, Tape and Reel")
      (fields (field (name "CAPACITANCE") "1 uF") (field (name "TOLERANCE") "10%"))
      (libsource (lib "Altium Content Vault") (part "CMP-1663-00006-2"))
    )
    (comp (ref "C77")
      (value "CGB2A1X5R1E105K033BC")
      (footprint "CAPC1005X33X10LL5")
      (description "Chip Capacitor, 1 uF, +/- 10%, 25 V, -55 to 85 degC, 0402 (1005 Metric), RoHS, Tape and Reel")
      (fields (field (name "CAPACITANCE") "1 uF") (field (name "TOLERANCE") "10%"))
      (libsource (lib "Altium Content Vault") (part "CMP-1663-00006-2"))
    )
    (comp (ref "C78")
      (value "CGB2A1X5R1E105K033BC")
      (footprint "CAPC1005X33X10LL5")
      (description "Chip Capacitor, 1 uF, +/- 10%, 25 V, -55 to 85 degC, 0402 (1005 Metric), RoHS, Tape and Reel")
      (fields (field (name "CAPACITANCE") "1 uF") (field (name "TOLERANCE") "10%"))
      (libsource (lib "Altium Content Vault") (part "CMP-1663-00006-2"))
    )
    (comp (ref "C79")
      (value "CGB2A1X5R1E105K033BC")
      (footprint "CAPC1005X33X10LL5")
      (description "Chip Capacitor, 1 uF, +/- 10%, 25 V, -55 to 85 degC, 0402 (1005 Metric), RoHS, Tape and Reel")
      (fields (field (name "CAPACITANCE") "1 uF") (field (name "TOLERANCE") "10%"))
      (libsource (lib "Altium Content Vault") (part "CMP-1663-00006-2"))
    )
    (comp (ref "C80")
      (value "CGB2A1X5R1E105K033BC")
      (footprint "CAPC1005X33X10LL5")
      (description "Chip Capacitor, 1 uF, +/- 10%, 25 V, -55 to 85 degC, 0402 (1005 Metric), RoHS, Tape and Reel")
      (fields (field (name "CAPACITANCE") "1 uF") (field (name "TOLERANCE") "10%"))
      (libsource (lib "Altium Content Vault") (part "CMP-1663-00006-2"))
    )
    (comp (ref "C81")
      (value "CGB2A1X5R1E105K033BC")
      (footprint "CAPC1005X33X10LL5")
      (description "Chip Capacitor, 1 uF, +/- 10%, 25 V, -55 to 85 degC, 0402 (1005 Metric), RoHS, Tape and Reel")
      (fields (field (name "CAPACITANCE") "1 uF") (field (name "TOLERANCE") "10%"))
      (libsource (lib "Altium Content Vault") (part "CMP-1663-00006-2"))
    )
  )
  (nets
    (net (code "1") (name "/VDD") (class "Default")
      (node (ref "C10") (pin "1") (pinfunction "1_1") (pintype "passive"))
      (node (ref "C11") (pin "1") (pinfunction "1_1") (pintype "passive"))
      (node (ref "C12") (pin "1") (pinfunction "1_1") (pintype "passive"))
      (node (ref "C13") (pin "2") (pinfunction "2_2") (pintype "passive"))
      (node (ref "C14") (pin "2") (pinfunction "2_2") (pintype "passive"))
      (node (ref "C15") (pin "2") (pinfunction "2_2") (pintype "passive"))
      (node (ref "C16") (pin "2") (pinfunction "2_2") (pintype "passive"))
      (node (ref "C17") (pin "2") (pinfunction "2_2") (pintype "passive"))
      (node (ref "C18") (pin "2") (pinfunction "2_2") (pintype "passive"))
      (node (ref "C19") (pin "2") (pinfunction "2_2") (pintype "passive"))
      (node (ref "C20") (pin "2") (pinfunction "2_2") (pintype "passive"))
      (node (ref "C21") (pin "2") (pinfunction "2_2") (pintype "passive"))
      (node (ref "C22") (pin "2") (pinfunction "2_2") (pintype "passive"))
      (node (ref "C23") (pin "1") (pinfunction "1_1") (pintype "passive"))
      (node (ref "C24") (pin "1") (pinfunction "1_1") (pintype "passive"))
      (node (ref "C25") (pin "1") (pinfunction "1_1") (pintype "passive"))
      (node (ref "C26") (pin "1") (pinfunction "1_1") (pintype "passive"))
      (node (ref "C27") (pin "1") (pinfunction "1_1") (pintype "passive"))
      (node (ref "C28") (pin "1") (pinfunction "1_1") (pintype "passive"))
      (node (ref "C29") (pin "1") (pinfunction "1_1") (pintype "passive"))
      (node (ref "C5") (pin "1") (pinfunction "1_1") (pintype "passive"))
      (node (ref "C56") (pin "1") (pinfunction "1_1") (pintype "passive"))
      (node (ref "C57") (pin "1") (pinfunction "1_1") (pintype "passive"))
      (node (ref "C58") (pin "2") (pinfunction "2_2") (pintype "passive"))
      (node (ref "C59") (pin "2") (pinfunction "2_2") (pintype "passive"))
      (node (ref "C6") (pin "1") (pinfunction "1_1") (pintype "passive"))
      (node (ref "C60") (pin "2") (pinfunction "2_2") (pintype "passive"))
      (node (ref "C61") (pin "2") (pinfunction "2_2") (pintype "passive"))
      (node (ref "C62") (pin "2") (pinfunction "2_2") (pintype "passive"))
      (node (ref "C63") (pin "2") (pinfunction "2_2") (pintype "passive"))
      (node (ref "C64") (pin "2") (pinfunction "2_2") (pintype "passive"))
      (node (ref "C65") (pin "2") (pinfunction "2_2") (pintype "passive"))
      (node (ref "C66") (pin "2") (pinfunction "2_2") (pintype "passive"))
      (node (ref "C67") (pin "2") (pinfunction "2_2") (pintype "passive"))
      (node (ref "C68") (pin "2") (pinfunction "2_2") (pintype "passive"))
      (node (ref "C69") (pin "2") (pinfunction "2_2") (pintype "passive"))
      (node (ref "C7") (pin "1") (pinfunction "1_1") (pintype "passive"))
      (node (ref "C70") (pin "2") (pinfunction "2_2") (pintype "passive"))
      (node (ref "C71") (pin "2") (pinfunction "2_2") (pintype "passive"))
      (node (ref "C72") (pin "2") (pinfunction "2_2") (pintype "passive"))
      (node (ref "C73") (pin "2") (pinfunction "2_2") (pintype "passive"))
      (node (ref "C74") (pin "2") (pinfunction "2_2") (pintype "passive"))
      (node (ref "C75") (pin "2") (pinfunction "2_2") (pintype "passive"))
      (node (ref "C76") (pin "2") (pinfunction "2_2") (pintype "passive"))
      (node (ref "C77") (pin "2") (pinfunction "2_2") (pintype "passive"))
      (node (ref "C78") (pin "2") (pinfunction "2_2") (pintype "passive"))
      (node (ref "C79") (pin "2") (pinfunction "2_2") (pintype "passive"))
      (node (ref "C8") (pin "1") (pinfunction "1_1") (pintype "passive"))
      (node (ref "C80") (pin "2") (pinfunction "2_2") (pintype "passive"))
      (node (ref "C81") (pin "2") (pinfunction "2_2") (pintype "passive"))
      (node (ref "C9") (pin "1") (pinfunction "1_1") (pintype "passive"))
    )
    (net (code "2") (name "/VPP") (class "Default")
      (node (ref "C30") (pin "2") (pinfunction "2_2") (pintype "passive"))
      (node (ref "C31") (pin "2") (pinfunction "2_2") (pintype "passive"))
      (node (ref "C32") (pin "2") (pinfunction "2_2") (pintype "passive"))
      (node (ref "C33") (pin "2") (pinfunction "2_2") (pintype "passive"))
      (node (ref "C34") (pin "2") (pinfunction "2_2") (pintype "passive"))
      (node (ref "C35") (pin "2") (pinfunction "2_2") (pintype "passive"))
      (node (ref "C36") (pin "2") (pinfunction "2_2") (pintype "passive"))
      (node (ref "C37") (pin "2") (pinfunction "2_2") (pintype "passive"))
      (node (ref "C38") (pin "2") (pinfunction "2_2") (pintype "passive"))
      (node (ref "C39") (pin "2") (pinfunction "2_2") (pintype "passive"))
      (node (ref "C40") (pin "2") (pinfunction "2_2") (pintype "passive"))
      (node (ref "C41") (pin "2") (pinfunction "2_2") (pintype "passive"))
      (node (ref "C42") (pin "2") (pinfunction "2_2") (pintype "passive"))
      (node (ref "C43") (pin "2") (pinfunction "2_2") (pintype "passive"))
      (node (ref "C44") (pin "2") (pinfunction "2_2") (pintype "passive"))
      (node (ref "C45") (pin "2") (pinfunction "2_2") (pintype "passive"))
      (node (ref "C46") (pin "2") (pinfunction "2_2") (pintype "passive"))
      (node (ref "C47") (pin "2") (pinfunction "2_2") (pintype "passive"))
      (node (ref "C48") (pin "2") (pinfunction "2_2") (pintype "passive"))
      (node (ref "C49") (pin "2") (pinfunction "2_2") (pintype "passive"))
      (node (ref "C50") (pin "2") (pinfunction "2_2") (pintype "passive"))
      (node (ref "C51") (pin "2") (pinfunction "2_2") (pintype "passive"))
      (node (ref "C52") (pin "2") (pinfunction "2_2") (pintype "passive"))
      (node (ref "C53") (pin "2") (pinfunction "2_2") (pintype "passive"))
      (node (ref "C54") (pin "2") (pinfunction "2_2") (pintype "passive"))
      (node (ref "C55") (pin "2") (pinfunction "2_2") (pintype "passive"))
    )
    (net (code "3") (name "/VREFCA") (class "Default")
      (node (ref "C10") (pin "2") (pinfunction "2_2") (pintype "passive"))
      (node (ref "C11") (pin "2") (pinfunction "2_2") (pintype "passive"))
      (node (ref "C12") (pin "2") (pinfunction "2_2") (pintype "passive"))
      (node (ref "C5") (pin "2") (pinfunction "2_2") (pintype "passive"))
      (node (ref "C6") (pin "2") (pinfunction "2_2") (pintype "passive"))
      (node (ref "C7") (pin "2") (pinfunction "2_2") (pintype "passive"))
      (node (ref "C8") (pin "2") (pinfunction "2_2") (pintype "passive"))
      (node (ref "C9") (pin "2") (pinfunction "2_2") (pintype "passive"))
    )
    (net (code "4") (name "/VTT") (class "Default")
      (node (ref "C23") (pin "2") (pinfunction "2_2") (pintype "passive"))
      (node (ref "C24") (pin "2") (pinfunction "2_2") (pintype "passive"))
      (node (ref "C25") (pin "2") (pinfunction "2_2") (pintype "passive"))
      (node (ref "C26") (pin "2") (pinfunction "2_2") (pintype "passive"))
      (node (ref "C27") (pin "2") (pinfunction "2_2") (pintype "passive"))
      (node (ref "C28") (pin "2") (pinfunction "2_2") (pintype "passive"))
      (node (ref "C29") (pin "2") (pinfunction "2_2") (pintype "passive"))
      (node (ref "C56") (pin "2") (pinfunction "2_2") (pintype "passive"))
      (node (ref "C57") (pin "2") (pinfunction "2_2") (pintype "passive"))
    )
    (net (code "5") (name "GND") (class "Default")
      (node (ref "C13") (pin "1") (pinfunction "1_1") (pintype "passive"))
      (node (ref "C14") (pin "1") (pinfunction "1_1") (pintype "passive"))
      (node (ref "C15") (pin "1") (pinfunction "1_1") (pintype "passive"))
      (node (ref "C16") (pin "1") (pinfunction "1_1") (pintype "passive"))
      (node (ref "C17") (pin "1") (pinfunction "1_1") (pintype "passive"))
      (node (ref "C18") (pin "1") (pinfunction "1_1") (pintype "passive"))
      (node (ref "C19") (pin "1") (pinfunction "1_1") (pintype "passive"))
      (node (ref "C20") (pin "1") (pinfunction "1_1") (pintype "passive"))
      (node (ref "C21") (pin "1") (pinfunction "1_1") (pintype "passive"))
      (node (ref "C22") (pin "1") (pinfunction "1_1") (pintype "passive"))
      (node (ref "C30") (pin "1") (pinfunction "1_1") (pintype "passive"))
      (node (ref "C31") (pin "1") (pinfunction "1_1") (pintype "passive"))
      (node (ref "C32") (pin "1") (pinfunction "1_1") (pintype "passive"))
      (node (ref "C33") (pin "1") (pinfunction "1_1") (pintype "passive"))
      (node (ref "C34") (pin "1") (pinfunction "1_1") (pintype "passive"))
      (node (ref "C35") (pin "1") (pinfunction "1_1") (pintype "passive"))
      (node (ref "C36") (pin "1") (pinfunction "1_1") (pintype "passive"))
      (node (ref "C37") (pin "1") (pinfunction "1_1") (pintype "passive"))
      (node (ref "C38") (pin "1") (pinfunction "1_1") (pintype "passive"))
      (node (ref "C39") (pin "1") (pinfunction "1_1") (pintype "passive"))
      (node (ref "C40") (pin "1") (pinfunction "1_1") (pintype "passive"))
      (node (ref "C41") (pin "1") (pinfunction "1_1") (pintype "passive"))
      (node (ref "C42") (pin "1") (pinfunction "1_1") (pintype "passive"))
      (node (ref "C43") (pin "1") (pinfunction "1_1") (pintype "passive"))
      (node (ref "C44") (pin "1") (pinfunction "1_1") (pintype "passive"))
      (node (ref "C45") (pin "1") (pinfunction "1_1") (pintype "passive"))
      (node (ref "C46") (pin "1") (pinfunction "1_1") (pintype "passive"))
      (node (ref "C47") (pin "1") (pinfunction "1_1") (pintype "passive"))
      (node (ref "C48") (pin "1") (pinfunction "1_1") (pintype "passive"))
      (node (ref "C49") (pin "1") (pinfunction "1_1") (pintype "passive"))
      (node (ref "C50") (pin "1") (pinfunction "1_1") (pintype "passive"))
      (node (ref "C51") (pin "1") (pinfunction "1_1") (pintype "passive"))
      (node (ref "C52") (pin "1") (pinfunction "1_1") (pintype "passive"))
      (node (ref "C53") (pin "1") (pinfunction "1_1") (pintype "passive"))
      (node (ref "C54") (pin "1") (pinfunction "1_1") (pintype "passive"))
      (node (ref "C55") (pin "1") (pinfunction "1_1") (pintype "passive"))
      (node (ref "C58") (pin "1") (pinfunction "1_1") (pintype "passive"))
      (node (ref "C59") (pin "1") (pinfunction "1_1") (pintype "passive"))
      (node (ref "C60") (pin "1") (pinfunction "1_1") (pintype "passive"))
      (node (ref "C61") (pin "1") (pinfunction "1_1") (pintype "passive"))
      (node (ref "C62") (pin "1") (pinfunction "1_1") (pintype "passive"))
      (node (ref "C63") (pin "1") (pinfunction "1_1") (pintype "passive"))
      (node (ref "C64") (pin "1") (pinfunction "1_1") (pintype "passive"))
      (node (ref "C65") (pin "1") (pinfunction "1_1") (pintype "passive"))
      (node (ref "C66") (pin "1") (pinfunction "1_1") (pintype "passive"))
      (node (ref "C67") (pin "1") (pinfunction "1_1") (pintype "passive"))
      (node (ref "C68") (pin "1") (pinfunction "1_1") (pintype "passive"))
      (node (ref "C69") (pin "1") (pinfunction "1_1") (pintype "passive"))
      (node (ref "C70") (pin "1") (pinfunction "1_1") (pintype "passive"))
      (node (ref "C71") (pin "1") (pinfunction "1_1") (pintype "passive"))
      (node (ref "C72") (pin "1") (pinfunction "1_1") (pintype "passive"))
      (node (ref "C73") (pin "1") (pinfunction "1_1") (pintype "passive"))
      (node (ref "C74") (pin "1") (pinfunction "1_1") (pintype "passive"))
      (node (ref "C75") (pin "1") (pinfunction "1_1") (pintype "passive"))
      (node (ref "C76") (pin "1") (pinfunction "1_1") (pintype "passive"))
      (node (ref "C77") (pin "1") (pinfunction "1_1") (pintype "passive"))
      (node (ref "C78") (pin "1") (pinfunction "1_1") (pintype "passive"))
      (node (ref "C79") (pin "1") (pinfunction "1_1") (pintype "passive"))
      (node (ref "C80") (pin "1") (pinfunction "1_1") (pintype "passive"))
      (node (ref "C81") (pin "1") (pinfunction "1_1") (pintype "passive"))
    )
  )
)
